# QSPI_soic16.net
KiCad netlist of a schematic drawn in Altium Designer
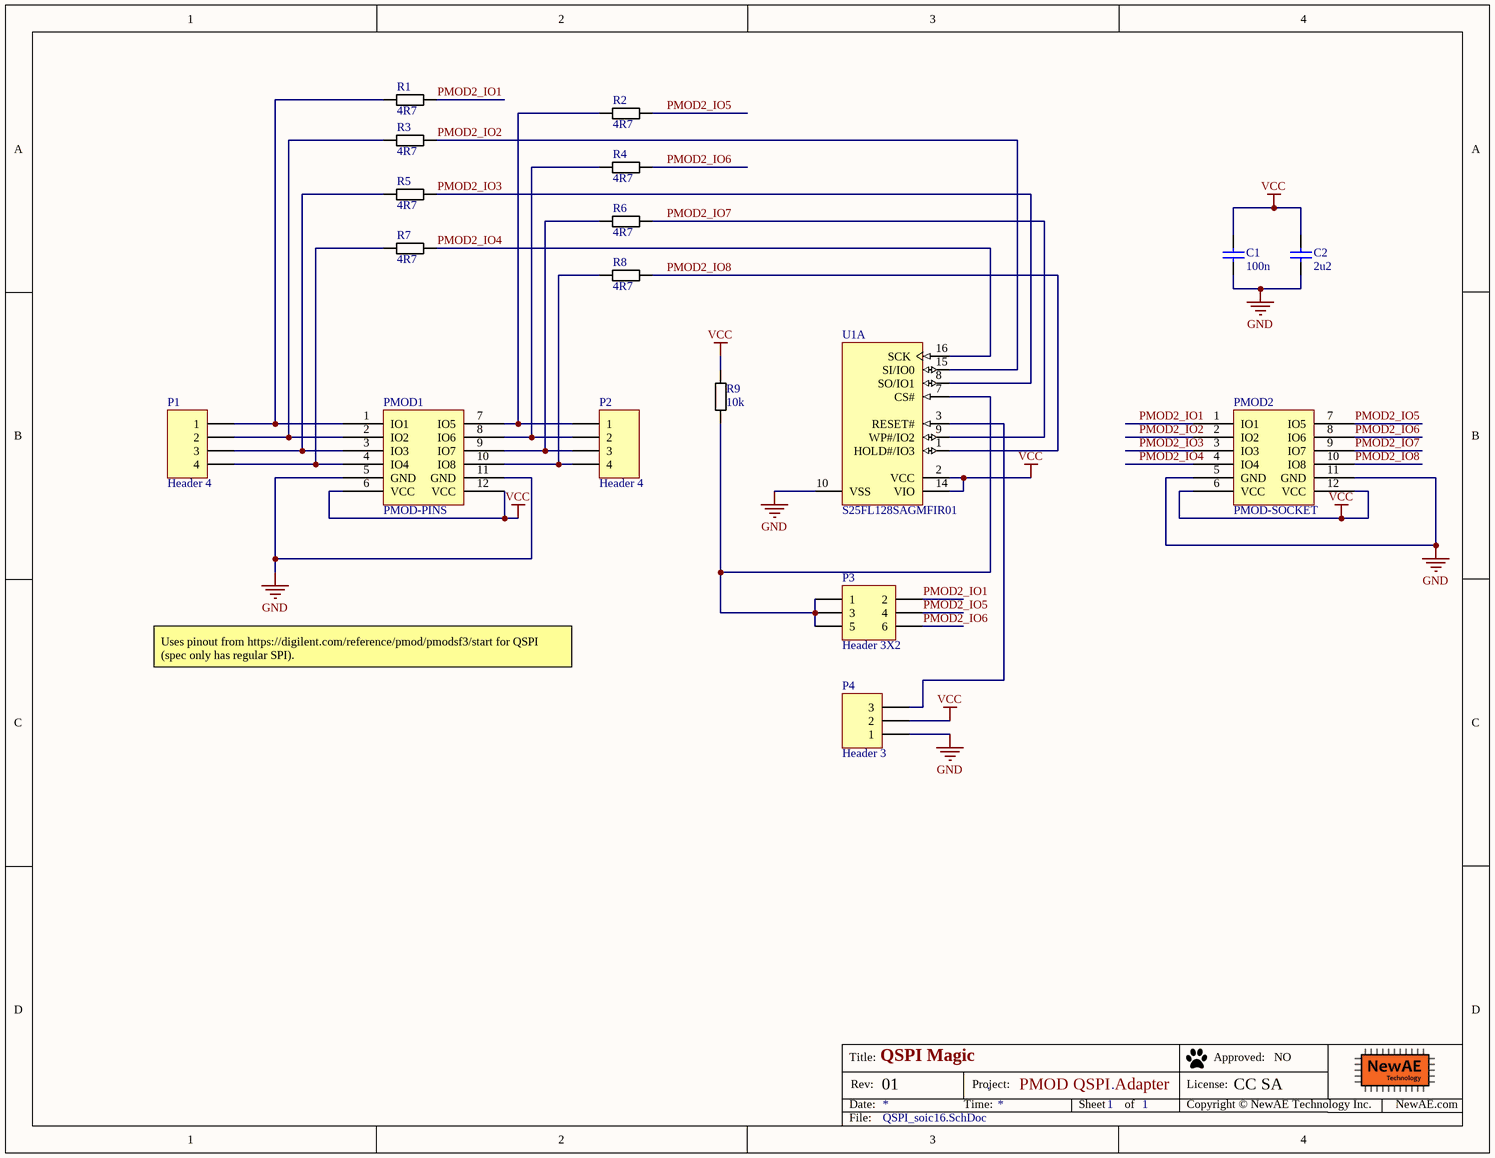
[diagram p0: QSPI_soic16.SchDoc]

(export (version "E")
  (design (tool "Eeschema 10.0.6"))
  (components
    (comp (ref "C1")
      (value "100n")
      (footprint "CAPC0603_M")
      (description "100n, 0603")
      (fields (field (name "PART NUMBER") "CCHIP-100n-0603"))
      (libsource (lib "NewAE_AltiumLib") (part "CAP"))
    )
    (comp (ref "C2")
      (value "2u2")
      (footprint "CAPC0603_M")
      (description "2u2, 0603")
      (fields (field (name "PART NUMBER") "CCHIP-2u2-0603"))
      (libsource (lib "NewAE_AltiumLib") (part "CAP"))
    )
    (comp (ref "P1")
      (value "Header 4")
      (footprint "HDR1X4")
      (description "Header, 4-Pin")
      (fields (field (name "PUBLISHER") "Altium Limited"))
      (libsource (lib "") (part "Header 4_1"))
    )
    (comp (ref "P2")
      (value "Header 4")
      (footprint "HDR1X4")
      (description "Header, 4-Pin")
      (fields (field (name "PUBLISHER") "Altium Limited"))
      (libsource (lib "Miscellaneous Connectors") (part "Header 4"))
    )
    (comp (ref "P3")
      (value "Header 3X2")
      (footprint "HDR2X3")
      (description "Header, 3-Pin, Dual row")
      (fields (field (name "PUBLISHER") "Altium Limited"))
      (libsource (lib "NewAE Technology") (part "Header 3X2H"))
    )
    (comp (ref "P4")
      (value "Header 3")
      (footprint "HDR1X3")
      (description "Header, 3-Pin")
      (fields
        (field (name "PUBLISHER") "Altium Limited")
        (field (name "SOURCE") "CW313_20pinToTarget.SCHLIB")
      )
      (libsource (lib "NewAE Technology") (part "Header 3"))
    )
    (comp (ref "PMOD1")
      (value "PMOD-PINS")
      (footprint "PMOD-68021-212HLF-MALE")
      (fields (field (name "PART NUMBER") "PMOD_2ROW_MALERATH"))
      (libsource (lib "NewAE_AltiumLib") (part "12PIN_RA_FEMALE"))
    )
    (comp (ref "PMOD2")
      (value "PMOD-SOCKET")
      (footprint "SAMTEC_SSW_106_02_X_D_RA_PMOD")
      (fields (field (name "PART NUMBER") "PMOD_2ROW_FEMALERATH"))
      (libsource (lib "NewAE_AltiumLib") (part "12PIN_RA_FEMALE"))
    )
    (comp (ref "R1")
      (value "4R7")
      (footprint "RESC1608X55N")
      (description "4R7 res, 0603, 1%, 1/10W")
      (fields (field (name "PART NUMBER") "RCHIP-4R7-0603") (field (name "TOLERANCE") "1%"))
      (libsource (lib "NewAE_AltiumLib") (part "RES-EU"))
    )
    (comp (ref "R2")
      (value "4R7")
      (footprint "RESC1608X55N")
      (description "4R7 res, 0603, 1%, 1/10W")
      (fields (field (name "PART NUMBER") "RCHIP-4R7-0603") (field (name "TOLERANCE") "1%"))
      (libsource (lib "NewAE_AltiumLib") (part "RES-EU"))
    )
    (comp (ref "R3")
      (value "4R7")
      (footprint "RESC1608X55N")
      (description "4R7 res, 0603, 1%, 1/10W")
      (fields (field (name "PART NUMBER") "RCHIP-4R7-0603") (field (name "TOLERANCE") "1%"))
      (libsource (lib "NewAE_AltiumLib") (part "RES-EU"))
    )
    (comp (ref "R4")
      (value "4R7")
      (footprint "RESC1608X55N")
      (description "4R7 res, 0603, 1%, 1/10W")
      (fields (field (name "PART NUMBER") "RCHIP-4R7-0603") (field (name "TOLERANCE") "1%"))
      (libsource (lib "NewAE_AltiumLib") (part "RES-EU"))
    )
    (comp (ref "R5")
      (value "4R7")
      (footprint "RESC1608X55N")
      (description "4R7 res, 0603, 1%, 1/10W")
      (fields (field (name "PART NUMBER") "RCHIP-4R7-0603") (field (name "TOLERANCE") "1%"))
      (libsource (lib "NewAE_AltiumLib") (part "RES-EU"))
    )
    (comp (ref "R6")
      (value "4R7")
      (footprint "RESC1608X55N")
      (description "4R7 res, 0603, 1%, 1/10W")
      (fields (field (name "PART NUMBER") "RCHIP-4R7-0603") (field (name "TOLERANCE") "1%"))
      (libsource (lib "NewAE_AltiumLib") (part "RES-EU"))
    )
    (comp (ref "R7")
      (value "4R7")
      (footprint "RESC1608X55N")
      (description "4R7 res, 0603, 1%, 1/10W")
      (fields (field (name "PART NUMBER") "RCHIP-4R7-0603") (field (name "TOLERANCE") "1%"))
      (libsource (lib "NewAE_AltiumLib") (part "RES-EU"))
    )
    (comp (ref "R8")
      (value "4R7")
      (footprint "RESC1608X55N")
      (description "4R7 res, 0603, 1%, 1/10W")
      (fields (field (name "PART NUMBER") "RCHIP-4R7-0603") (field (name "TOLERANCE") "1%"))
      (libsource (lib "NewAE_AltiumLib") (part "RES-EU"))
    )
    (comp (ref "R9")
      (value "10k")
      (footprint "RESC1608X55N")
      (description "10k res, 0603, 1%, 1/10W")
      (fields (field (name "PART NUMBER") "RCHIP-10K-0603") (field (name "TOLERANCE") "1%"))
      (libsource (lib "") (part "RES-EU_1"))
    )
    (comp (ref "U1")
      (value "S25FL128SAGMFIR01")
      (footprint "SPSN-SOIC-16_N")
      (fields (field (name "MANUFACTURER") "Spansion"))
      (libsource (lib "Altium Content Vault") (part "SPSN-S25FL128S-16_A"))
    )
  )
  (nets
    (net (code "1") (name "/PMOD2_IO1") (class "Default")
      (node (ref "P3") (pin "2") (pinfunction "2_2") (pintype "passive"))
      (node (ref "PMOD2") (pin "1") (pinfunction "IO1_1") (pintype "passive"))
      (node (ref "R1") (pin "2") (pinfunction "2_2") (pintype "passive"))
    )
    (net (code "2") (name "/PMOD2_IO2") (class "Default")
      (node (ref "PMOD2") (pin "2") (pinfunction "IO2_2") (pintype "passive"))
      (node (ref "R3") (pin "2") (pinfunction "2_2") (pintype "passive"))
      (node (ref "U1") (pin "15") (pinfunction "SI/IO0_15") (pintype "bidirectional"))
    )
    (net (code "3") (name "/PMOD2_IO3") (class "Default")
      (node (ref "PMOD2") (pin "3") (pinfunction "IO3_3") (pintype "passive"))
      (node (ref "R5") (pin "2") (pinfunction "2_2") (pintype "passive"))
      (node (ref "U1") (pin "8") (pinfunction "SO/IO1_8") (pintype "bidirectional"))
    )
    (net (code "4") (name "/PMOD2_IO4") (class "Default")
      (node (ref "PMOD2") (pin "4") (pinfunction "IO4_4") (pintype "passive"))
      (node (ref "R7") (pin "2") (pinfunction "2_2") (pintype "passive"))
      (node (ref "U1") (pin "16") (pinfunction "SCK_16") (pintype "input"))
    )
    (net (code "5") (name "/PMOD2_IO5") (class "Default")
      (node (ref "P3") (pin "4") (pinfunction "4_4") (pintype "passive"))
      (node (ref "PMOD2") (pin "7") (pinfunction "IO5_7") (pintype "passive"))
      (node (ref "R2") (pin "2") (pinfunction "2_2") (pintype "passive"))
    )
    (net (code "6") (name "/PMOD2_IO6") (class "Default")
      (node (ref "P3") (pin "6") (pinfunction "6_6") (pintype "passive"))
      (node (ref "PMOD2") (pin "8") (pinfunction "IO6_8") (pintype "passive"))
      (node (ref "R4") (pin "2") (pinfunction "2_2") (pintype "passive"))
    )
    (net (code "7") (name "/PMOD2_IO7") (class "Default")
      (node (ref "PMOD2") (pin "9") (pinfunction "IO7_9") (pintype "passive"))
      (node (ref "R6") (pin "2") (pinfunction "2_2") (pintype "passive"))
      (node (ref "U1") (pin "9") (pinfunction "WP#/IO2_9") (pintype "bidirectional"))
    )
    (net (code "8") (name "/PMOD2_IO8") (class "Default")
      (node (ref "PMOD2") (pin "10") (pinfunction "IO8_10") (pintype "passive"))
      (node (ref "R8") (pin "2") (pinfunction "2_2") (pintype "passive"))
      (node (ref "U1") (pin "1") (pinfunction "HOLD#/IO3_1") (pintype "bidirectional"))
    )
    (net (code "9") (name "GND") (class "Default")
      (node (ref "C1") (pin "2") (pinfunction "2_2") (pintype "passive"))
      (node (ref "C2") (pin "2") (pinfunction "2_2") (pintype "passive"))
      (node (ref "P4") (pin "1") (pinfunction "1_1") (pintype "passive"))
      (node (ref "PMOD1") (pin "11") (pinfunction "GND_11") (pintype "passive"))
      (node (ref "PMOD1") (pin "5") (pinfunction "GND_5") (pintype "passive"))
      (node (ref "PMOD2") (pin "11") (pinfunction "GND_11") (pintype "passive"))
      (node (ref "PMOD2") (pin "5") (pinfunction "GND_5") (pintype "passive"))
      (node (ref "U1") (pin "10") (pinfunction "VSS_10") (pintype "power_in"))
    )
    (net (code "10") (name "Net-(PMOD1-IO1)") (class "Default")
      (node (ref "P1") (pin "1") (pinfunction "1_1") (pintype "passive"))
      (node (ref "PMOD1") (pin "1") (pinfunction "IO1_1") (pintype "passive"))
      (node (ref "R1") (pin "1") (pinfunction "1_1") (pintype "passive"))
    )
    (net (code "11") (name "Net-(PMOD1-IO2)") (class "Default")
      (node (ref "P1") (pin "2") (pinfunction "2_2") (pintype "passive"))
      (node (ref "PMOD1") (pin "2") (pinfunction "IO2_2") (pintype "passive"))
      (node (ref "R3") (pin "1") (pinfunction "1_1") (pintype "passive"))
    )
    (net (code "12") (name "Net-(PMOD1-IO3)") (class "Default")
      (node (ref "P1") (pin "3") (pinfunction "3_3") (pintype "passive"))
      (node (ref "PMOD1") (pin "3") (pinfunction "IO3_3") (pintype "passive"))
      (node (ref "R5") (pin "1") (pinfunction "1_1") (pintype "passive"))
    )
    (net (code "13") (name "Net-(PMOD1-IO4)") (class "Default")
      (node (ref "P1") (pin "4") (pinfunction "4_4") (pintype "passive"))
      (node (ref "PMOD1") (pin "4") (pinfunction "IO4_4") (pintype "passive"))
      (node (ref "R7") (pin "1") (pinfunction "1_1") (pintype "passive"))
    )
    (net (code "14") (name "Net-(PMOD1-IO5)") (class "Default")
      (node (ref "P2") (pin "1") (pinfunction "1_1") (pintype "passive"))
      (node (ref "PMOD1") (pin "7") (pinfunction "IO5_7") (pintype "passive"))
      (node (ref "R2") (pin "1") (pinfunction "1_1") (pintype "passive"))
    )
    (net (code "15") (name "Net-(PMOD1-IO6)") (class "Default")
      (node (ref "P2") (pin "2") (pinfunction "2_2") (pintype "passive"))
      (node (ref "PMOD1") (pin "8") (pinfunction "IO6_8") (pintype "passive"))
      (node (ref "R4") (pin "1") (pinfunction "1_1") (pintype "passive"))
    )
    (net (code "16") (name "Net-(PMOD1-IO7)") (class "Default")
      (node (ref "P2") (pin "3") (pinfunction "3_3") (pintype "passive"))
      (node (ref "PMOD1") (pin "9") (pinfunction "IO7_9") (pintype "passive"))
      (node (ref "R6") (pin "1") (pinfunction "1_1") (pintype "passive"))
    )
    (net (code "17") (name "Net-(PMOD1-IO8)") (class "Default")
      (node (ref "P2") (pin "4") (pinfunction "4_4") (pintype "passive"))
      (node (ref "PMOD1") (pin "10") (pinfunction "IO8_10") (pintype "passive"))
      (node (ref "R8") (pin "1") (pinfunction "1_1") (pintype "passive"))
    )
    (net (code "18") (name "Net-(U1A-CS#)") (class "Default")
      (node (ref "P3") (pin "1") (pinfunction "1_1") (pintype "passive"))
      (node (ref "P3") (pin "3") (pinfunction "3_3") (pintype "passive"))
      (node (ref "P3") (pin "5") (pinfunction "5_5") (pintype "passive"))
      (node (ref "R9") (pin "1") (pinfunction "1_1") (pintype "passive"))
      (node (ref "U1") (pin "7") (pinfunction "CS#_7") (pintype "input"))
    )
    (net (code "19") (name "Net-(U1A-RESET#)") (class "Default")
      (node (ref "P4") (pin "3") (pinfunction "3_3") (pintype "passive"))
      (node (ref "U1") (pin "3") (pinfunction "RESET#_3") (pintype "input"))
    )
    (net (code "20") (name "VCC") (class "Default")
      (node (ref "C1") (pin "1") (pinfunction "1_1") (pintype "passive"))
      (node (ref "C2") (pin "1") (pinfunction "1_1") (pintype "passive"))
      (node (ref "P4") (pin "2") (pinfunction "2_2") (pintype "passive"))
      (node (ref "PMOD1") (pin "12") (pinfunction "VCC_12") (pintype "passive"))
      (node (ref "PMOD1") (pin "6") (pinfunction "VCC_6") (pintype "passive"))
      (node (ref "PMOD2") (pin "12") (pinfunction "VCC_12") (pintype "passive"))
      (node (ref "PMOD2") (pin "6") (pinfunction "VCC_6") (pintype "passive"))
      (node (ref "R9") (pin "2") (pinfunction "2_2") (pintype "passive"))
      (node (ref "U1") (pin "14") (pinfunction "VIO_14") (pintype "power_in"))
      (node (ref "U1") (pin "2") (pinfunction "VCC_2") (pintype "power_in"))
    )
  )
)
